# usb_relay_board.net
KiCad netlist of a schematic drawn in EAGLE
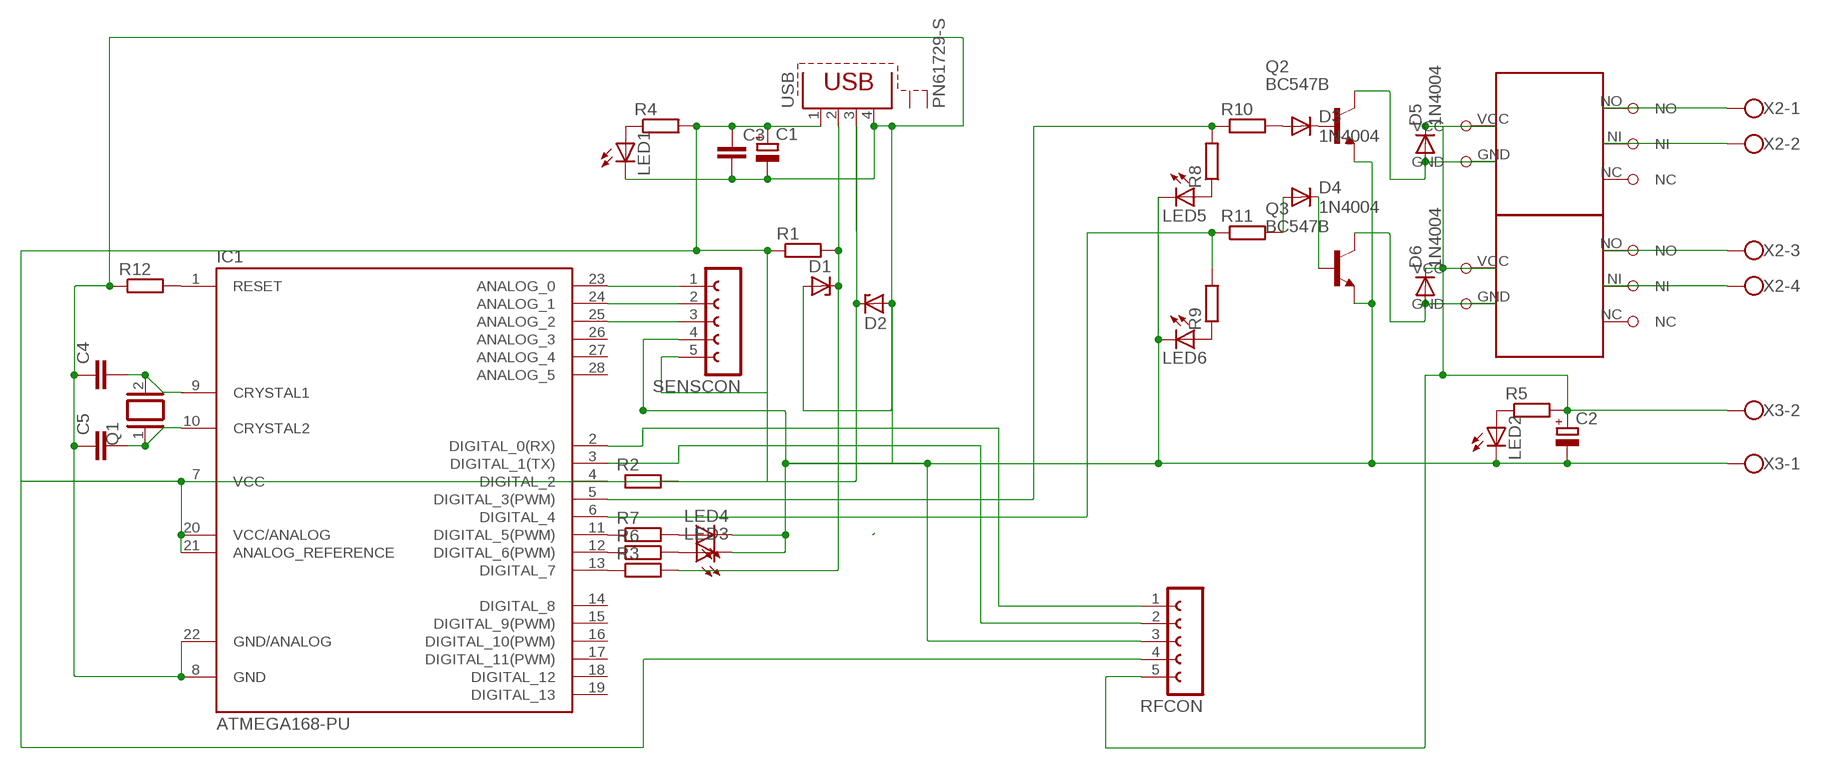
[diagram p0: schematic, sheet 1]

(export (version "E")
  (design (tool "Eeschema 10.0.6"))
  (components
    (comp (ref "C1")
      (value "CPOL-EUE2.5-7")
      (footprint "eagle-import:E2,5-7")
      (libsource (lib "eagle-import") (part "CPOL-EUE2.5-7"))
    )
    (comp (ref "C2")
      (value "CPOL-EUE5-10.5")
      (footprint "eagle-import:E5-10,5")
      (libsource (lib "eagle-import") (part "CPOL-EUE5-10.5"))
    )
    (comp (ref "C3")
      (value "C-EU075-032X103")
      (footprint "eagle-import:C075-032X103")
      (libsource (lib "eagle-import") (part "C-EU075-032X103"))
    )
    (comp (ref "C4")
      (value "C-EU075-032X103")
      (footprint "eagle-import:C075-032X103")
      (libsource (lib "eagle-import") (part "C-EU075-032X103"))
    )
    (comp (ref "C5")
      (value "C-EU075-032X103")
      (footprint "eagle-import:C075-032X103")
      (libsource (lib "eagle-import") (part "C-EU075-032X103"))
    )
    (comp (ref "D1")
      (value "ZENER-DIODEDO34-7")
      (footprint "eagle-import:DO34Z7")
      (libsource (lib "eagle-import") (part "ZENER-DIODEDO34-7"))
    )
    (comp (ref "D2")
      (value "ZENER-DIODEDO34-7")
      (footprint "eagle-import:DO34Z7")
      (libsource (lib "eagle-import") (part "ZENER-DIODEDO34-7"))
    )
    (comp (ref "D3")
      (value "1N4004")
      (footprint "eagle-import:DO41-10")
      (libsource (lib "eagle-import") (part "1N4004"))
    )
    (comp (ref "D4")
      (value "1N4004")
      (footprint "eagle-import:DO41-10")
      (libsource (lib "eagle-import") (part "1N4004"))
    )
    (comp (ref "D5")
      (value "1N4004")
      (footprint "eagle-import:DO41-10")
      (libsource (lib "eagle-import") (part "1N4004"))
    )
    (comp (ref "D6")
      (value "1N4004")
      (footprint "eagle-import:DO41-10")
      (libsource (lib "eagle-import") (part "1N4004"))
    )
    (comp (ref "IC1")
      (value "ATMEGA168-PU")
      (footprint "eagle-import:DIL28-3")
      (libsource (lib "eagle-import") (part "ATMEGA168-PU"))
    )
    (comp (ref "LED1")
      (value "LED3MM")
      (footprint "eagle-import:LED3MM")
      (libsource (lib "eagle-import") (part "LED3MM"))
    )
    (comp (ref "LED2")
      (value "LED3MM")
      (footprint "eagle-import:LED3MM")
      (libsource (lib "eagle-import") (part "LED3MM"))
    )
    (comp (ref "LED3")
      (value "LED3MM")
      (footprint "eagle-import:LED3MM")
      (libsource (lib "eagle-import") (part "LED3MM"))
    )
    (comp (ref "LED4")
      (value "LED3MM")
      (footprint "eagle-import:LED3MM")
      (libsource (lib "eagle-import") (part "LED3MM"))
    )
    (comp (ref "LED5")
      (value "LED3MM")
      (footprint "eagle-import:LED3MM")
      (libsource (lib "eagle-import") (part "LED3MM"))
    )
    (comp (ref "LED6")
      (value "LED3MM")
      (footprint "eagle-import:LED3MM")
      (libsource (lib "eagle-import") (part "LED3MM"))
    )
    (comp (ref "Q1")
      (value "XTAL/S")
      (footprint "eagle-import:QS")
      (libsource (lib "eagle-import") (part "XTAL/S"))
    )
    (comp (ref "Q2")
      (value "BC547B")
      (footprint "eagle-import:TO92")
      (libsource (lib "eagle-import") (part "BC547B"))
    )
    (comp (ref "Q3")
      (value "BC547B")
      (footprint "eagle-import:TO92")
      (libsource (lib "eagle-import") (part "BC547B"))
    )
    (comp (ref "R1")
      (value "R-EU_0204/7")
      (footprint "eagle-import:0204_7")
      (libsource (lib "eagle-import") (part "R-EU_0204/7"))
    )
    (comp (ref "R2")
      (value "R-EU_0204/7")
      (footprint "eagle-import:0204_7")
      (libsource (lib "eagle-import") (part "R-EU_0204/7"))
    )
    (comp (ref "R3")
      (value "R-EU_0204/7")
      (footprint "eagle-import:0204_7")
      (libsource (lib "eagle-import") (part "R-EU_0204/7"))
    )
    (comp (ref "R4")
      (value "R-EU_0204/7")
      (footprint "eagle-import:0204_7")
      (libsource (lib "eagle-import") (part "R-EU_0204/7"))
    )
    (comp (ref "R5")
      (value "R-EU_0204/7")
      (footprint "eagle-import:0204_7")
      (libsource (lib "eagle-import") (part "R-EU_0204/7"))
    )
    (comp (ref "R6")
      (value "R-EU_0204/7")
      (footprint "eagle-import:0204_7")
      (libsource (lib "eagle-import") (part "R-EU_0204/7"))
    )
    (comp (ref "R7")
      (value "R-EU_0204/7")
      (footprint "eagle-import:0204_7")
      (libsource (lib "eagle-import") (part "R-EU_0204/7"))
    )
    (comp (ref "R8")
      (value "R-EU_0204/7")
      (footprint "eagle-import:0204_7")
      (libsource (lib "eagle-import") (part "R-EU_0204/7"))
    )
    (comp (ref "R9")
      (value "R-EU_0204/7")
      (footprint "eagle-import:0204_7")
      (libsource (lib "eagle-import") (part "R-EU_0204/7"))
    )
    (comp (ref "R10")
      (value "R-EU_0204/7")
      (footprint "eagle-import:0204_7")
      (libsource (lib "eagle-import") (part "R-EU_0204/7"))
    )
    (comp (ref "R11")
      (value "R-EU_0204/7")
      (footprint "eagle-import:0204_7")
      (libsource (lib "eagle-import") (part "R-EU_0204/7"))
    )
    (comp (ref "R12")
      (value "R-EU_0204/7")
      (footprint "eagle-import:0204_7")
      (libsource (lib "eagle-import") (part "R-EU_0204/7"))
    )
    (comp (ref "RFCON")
      (value "FE05-1")
      (footprint "eagle-import:FE05-1")
      (libsource (lib "eagle-import") (part "FE05-1"))
    )
    (comp (ref "SENSCON")
      (value "FE05-1")
      (footprint "eagle-import:FE05-1")
      (libsource (lib "eagle-import") (part "FE05-1"))
    )
    (comp (ref "U$1")
      (value "RELAY")
      (footprint "eagle-import:RELAY")
      (libsource (lib "eagle-import") (part "RELAY"))
    )
    (comp (ref "U$2")
      (value "RELAY")
      (footprint "eagle-import:RELAY")
      (libsource (lib "eagle-import") (part "RELAY"))
    )
    (comp (ref "USB")
      (value "PN61729-S")
      (footprint "eagle-import:PN61729-S")
      (libsource (lib "eagle-import") (part "PN61729-S"))
    )
    (comp (ref "X2")
      (value "W237-4")
      (footprint "eagle-import:W237-4")
      (libsource (lib "eagle-import") (part "W237-4"))
    )
    (comp (ref "X3")
      (value "W237-102")
      (footprint "eagle-import:W237-102")
      (fields (field (name "MPN") "237-102"))
      (libsource (lib "eagle-import") (part "W237-102"))
    )
  )
  (nets
    (net (code "1") (name "Net-(D1-PadC)") (class "Default")
      (node (ref "D1") (pin "C") (pinfunction "C_C") (pintype "passive"))
      (node (ref "R1") (pin "2") (pinfunction "2_2") (pintype "passive"))
      (node (ref "R3") (pin "2") (pinfunction "2_2") (pintype "passive"))
      (node (ref "USB") (pin "2") (pinfunction "2_2") (pintype "passive"))
    )
    (net (code "2") (name "Net-(D2-PadC)") (class "Default")
      (node (ref "D2") (pin "C") (pinfunction "C_C") (pintype "passive"))
      (node (ref "R2") (pin "2") (pinfunction "2_2") (pintype "passive"))
      (node (ref "USB") (pin "3") (pinfunction "3_3") (pintype "passive"))
    )
    (net (code "3") (name "Net-(D3-PadA)") (class "Default")
      (node (ref "D3") (pin "A") (pinfunction "A_A") (pintype "passive"))
      (node (ref "R10") (pin "2") (pinfunction "2_2") (pintype "passive"))
    )
    (net (code "4") (name "Net-(D4-PadA)") (class "Default")
      (node (ref "D4") (pin "A") (pinfunction "A_A") (pintype "passive"))
      (node (ref "R11") (pin "2") (pinfunction "2_2") (pintype "passive"))
    )
    (net (code "5") (name "Net-(IC1-ANALOG_0)") (class "Default")
      (node (ref "IC1") (pin "23") (pinfunction "ANALOG_0_23") (pintype "bidirectional"))
      (node (ref "SENSCON") (pin "1") (pinfunction "1_1") (pintype "passive"))
    )
    (net (code "6") (name "Net-(IC1-ANALOG_1)") (class "Default")
      (node (ref "IC1") (pin "24") (pinfunction "ANALOG_1_24") (pintype "bidirectional"))
      (node (ref "SENSCON") (pin "2") (pinfunction "2_2") (pintype "passive"))
    )
    (net (code "7") (name "Net-(IC1-ANALOG_2)") (class "Default")
      (node (ref "IC1") (pin "25") (pinfunction "ANALOG_2_25") (pintype "bidirectional"))
      (node (ref "SENSCON") (pin "3") (pinfunction "3_3") (pintype "passive"))
    )
    (net (code "8") (name "Net-(IC1-ANALOG_REFERENCE)") (class "Default")
      (node (ref "C1") (pin "+") (pinfunction "+_+") (pintype "passive"))
      (node (ref "C3") (pin "1") (pinfunction "1_1") (pintype "passive"))
      (node (ref "IC1") (pin "20") (pinfunction "VCC/ANALOG_20") (pintype "passive"))
      (node (ref "IC1") (pin "21") (pinfunction "ANALOG_REFERENCE_21") (pintype "passive"))
      (node (ref "IC1") (pin "7") (pinfunction "VCC_7") (pintype "power_in"))
      (node (ref "R1") (pin "1") (pinfunction "1_1") (pintype "passive"))
      (node (ref "R4") (pin "2") (pinfunction "2_2") (pintype "passive"))
      (node (ref "SENSCON") (pin "5") (pinfunction "5_5") (pintype "passive"))
      (node (ref "USB") (pin "1") (pinfunction "1_1") (pintype "passive"))
    )
    (net (code "9") (name "Net-(IC1-CRYSTAL1)") (class "Default")
      (node (ref "C4") (pin "2") (pinfunction "2_2") (pintype "passive"))
      (node (ref "IC1") (pin "9") (pinfunction "CRYSTAL1_9") (pintype "bidirectional"))
      (node (ref "Q1") (pin "2") (pinfunction "2_2") (pintype "passive"))
    )
    (net (code "10") (name "Net-(IC1-CRYSTAL2)") (class "Default")
      (node (ref "C5") (pin "2") (pinfunction "2_2") (pintype "passive"))
      (node (ref "IC1") (pin "10") (pinfunction "CRYSTAL2_10") (pintype "bidirectional"))
      (node (ref "Q1") (pin "1") (pinfunction "1_1") (pintype "passive"))
    )
    (net (code "11") (name "Net-(IC1-DIGITAL_0(RX))") (class "Default")
      (node (ref "IC1") (pin "2") (pinfunction "DIGITAL_0(RX)_2") (pintype "bidirectional"))
      (node (ref "RFCON") (pin "1") (pinfunction "1_1") (pintype "passive"))
    )
    (net (code "12") (name "Net-(IC1-DIGITAL_1(TX))") (class "Default")
      (node (ref "IC1") (pin "3") (pinfunction "DIGITAL_1(TX)_3") (pintype "bidirectional"))
      (node (ref "RFCON") (pin "2") (pinfunction "2_2") (pintype "passive"))
    )
    (net (code "13") (name "Net-(IC1-DIGITAL_2)") (class "Default")
      (node (ref "IC1") (pin "4") (pinfunction "DIGITAL_2_4") (pintype "bidirectional"))
      (node (ref "R2") (pin "1") (pinfunction "1_1") (pintype "passive"))
    )
    (net (code "14") (name "Net-(IC1-DIGITAL_3(PWM))") (class "Default")
      (node (ref "IC1") (pin "5") (pinfunction "DIGITAL_3(PWM)_5") (pintype "bidirectional"))
      (node (ref "R10") (pin "1") (pinfunction "1_1") (pintype "passive"))
      (node (ref "R8") (pin "2") (pinfunction "2_2") (pintype "passive"))
    )
    (net (code "15") (name "Net-(IC1-DIGITAL_4)") (class "Default")
      (node (ref "IC1") (pin "6") (pinfunction "DIGITAL_4_6") (pintype "bidirectional"))
      (node (ref "R11") (pin "1") (pinfunction "1_1") (pintype "passive"))
      (node (ref "R9") (pin "2") (pinfunction "2_2") (pintype "passive"))
    )
    (net (code "16") (name "Net-(IC1-DIGITAL_5(PWM))") (class "Default")
      (node (ref "IC1") (pin "11") (pinfunction "DIGITAL_5(PWM)_11") (pintype "bidirectional"))
      (node (ref "R7") (pin "1") (pinfunction "1_1") (pintype "passive"))
    )
    (net (code "17") (name "Net-(IC1-DIGITAL_6(PWM))") (class "Default")
      (node (ref "IC1") (pin "12") (pinfunction "DIGITAL_6(PWM)_12") (pintype "bidirectional"))
      (node (ref "R6") (pin "1") (pinfunction "1_1") (pintype "passive"))
    )
    (net (code "18") (name "Net-(IC1-DIGITAL_7)") (class "Default")
      (node (ref "IC1") (pin "13") (pinfunction "DIGITAL_7_13") (pintype "bidirectional"))
      (node (ref "R3") (pin "1") (pinfunction "1_1") (pintype "passive"))
    )
    (net (code "19") (name "Net-(IC1-GND)") (class "Default")
      (node (ref "C1") (pin "-") (pinfunction "-_-") (pintype "passive"))
      (node (ref "C2") (pin "-") (pinfunction "-_-") (pintype "passive"))
      (node (ref "C3") (pin "2") (pinfunction "2_2") (pintype "passive"))
      (node (ref "C4") (pin "1") (pinfunction "1_1") (pintype "passive"))
      (node (ref "C5") (pin "1") (pinfunction "1_1") (pintype "passive"))
      (node (ref "D1") (pin "A") (pinfunction "A_A") (pintype "passive"))
      (node (ref "D2") (pin "A") (pinfunction "A_A") (pintype "passive"))
      (node (ref "IC1") (pin "22") (pinfunction "GND/ANALOG_22") (pintype "power_in"))
      (node (ref "IC1") (pin "8") (pinfunction "GND_8") (pintype "power_in"))
      (node (ref "LED1") (pin "K") (pinfunction "C_K") (pintype "passive"))
      (node (ref "LED2") (pin "K") (pinfunction "C_K") (pintype "passive"))
      (node (ref "LED3") (pin "K") (pinfunction "C_K") (pintype "passive"))
      (node (ref "LED4") (pin "K") (pinfunction "C_K") (pintype "passive"))
      (node (ref "LED5") (pin "K") (pinfunction "C_K") (pintype "passive"))
      (node (ref "LED6") (pin "K") (pinfunction "C_K") (pintype "passive"))
      (node (ref "Q2") (pin "1") (pinfunction "E_1") (pintype "passive"))
      (node (ref "Q3") (pin "1") (pinfunction "E_1") (pintype "passive"))
      (node (ref "R12") (pin "1") (pinfunction "1_1") (pintype "passive"))
      (node (ref "RFCON") (pin "3") (pinfunction "3_3") (pintype "passive"))
      (node (ref "SENSCON") (pin "4") (pinfunction "4_4") (pintype "passive"))
      (node (ref "USB") (pin "4") (pinfunction "4_4") (pintype "passive"))
      (node (ref "X3") (pin "1") (pinfunction "KL_1") (pintype "passive"))
    )
    (net (code "20") (name "Net-(IC1-RESET)") (class "Default")
      (node (ref "IC1") (pin "1") (pinfunction "RESET_1") (pintype "bidirectional"))
      (node (ref "R12") (pin "2") (pinfunction "2_2") (pintype "passive"))
    )
    (net (code "21") (name "Net-(LED1-PadA)") (class "Default")
      (node (ref "LED1") (pin "A") (pinfunction "A_A") (pintype "passive"))
      (node (ref "R4") (pin "1") (pinfunction "1_1") (pintype "passive"))
    )
    (net (code "22") (name "Net-(LED2-PadA)") (class "Default")
      (node (ref "LED2") (pin "A") (pinfunction "A_A") (pintype "passive"))
      (node (ref "R5") (pin "1") (pinfunction "1_1") (pintype "passive"))
    )
    (net (code "23") (name "Net-(LED3-PadA)") (class "Default")
      (node (ref "LED3") (pin "A") (pinfunction "A_A") (pintype "passive"))
      (node (ref "R6") (pin "2") (pinfunction "2_2") (pintype "passive"))
    )
    (net (code "24") (name "Net-(LED4-PadA)") (class "Default")
      (node (ref "LED4") (pin "A") (pinfunction "A_A") (pintype "passive"))
      (node (ref "R7") (pin "2") (pinfunction "2_2") (pintype "passive"))
    )
    (net (code "25") (name "Net-(LED5-PadA)") (class "Default")
      (node (ref "LED5") (pin "A") (pinfunction "A_A") (pintype "passive"))
      (node (ref "R8") (pin "1") (pinfunction "1_1") (pintype "passive"))
    )
    (net (code "26") (name "Net-(LED6-PadA)") (class "Default")
      (node (ref "LED6") (pin "A") (pinfunction "A_A") (pintype "passive"))
      (node (ref "R9") (pin "1") (pinfunction "1_1") (pintype "passive"))
    )
    (net (code "27") (name "Net-(Q2-B)") (class "Default")
      (node (ref "D3") (pin "C") (pinfunction "C_C") (pintype "passive"))
      (node (ref "Q2") (pin "2") (pinfunction "B_2") (pintype "passive"))
    )
    (net (code "28") (name "Net-(Q2-C)") (class "Default")
      (node (ref "D5") (pin "A") (pinfunction "A_A") (pintype "passive"))
      (node (ref "Q2") (pin "3") (pinfunction "C_3") (pintype "passive"))
      (node (ref "U$1") (pin "GND") (pinfunction "GND_GND") (pintype "bidirectional"))
    )
    (net (code "29") (name "Net-(Q3-B)") (class "Default")
      (node (ref "D4") (pin "C") (pinfunction "C_C") (pintype "passive"))
      (node (ref "Q3") (pin "2") (pinfunction "B_2") (pintype "passive"))
    )
    (net (code "30") (name "Net-(Q3-C)") (class "Default")
      (node (ref "D6") (pin "A") (pinfunction "A_A") (pintype "passive"))
      (node (ref "Q3") (pin "3") (pinfunction "C_3") (pintype "passive"))
      (node (ref "U$2") (pin "GND") (pinfunction "GND_GND") (pintype "bidirectional"))
    )
    (net (code "31") (name "Net-(X2A-KL)") (class "Default")
      (node (ref "U$1") (pin "NO") (pinfunction "NO_NO") (pintype "bidirectional"))
      (node (ref "X2") (pin "1") (pinfunction "KL_1") (pintype "passive"))
    )
    (net (code "32") (name "Net-(X2B-KL)") (class "Default")
      (node (ref "U$1") (pin "NI") (pinfunction "NI_NI") (pintype "bidirectional"))
      (node (ref "X2") (pin "2") (pinfunction "KL_2") (pintype "passive"))
    )
    (net (code "33") (name "Net-(X2C-KL)") (class "Default")
      (node (ref "U$2") (pin "NO") (pinfunction "NO_NO") (pintype "bidirectional"))
      (node (ref "X2") (pin "3") (pinfunction "KL_3") (pintype "passive"))
    )
    (net (code "34") (name "Net-(X2D-KL)") (class "Default")
      (node (ref "U$2") (pin "NI") (pinfunction "NI_NI") (pintype "bidirectional"))
      (node (ref "X2") (pin "4") (pinfunction "KL_4") (pintype "passive"))
    )
    (net (code "35") (name "Net-(X3B-KL)") (class "Default")
      (node (ref "C2") (pin "+") (pinfunction "+_+") (pintype "passive"))
      (node (ref "D5") (pin "C") (pinfunction "C_C") (pintype "passive"))
      (node (ref "D6") (pin "C") (pinfunction "C_C") (pintype "passive"))
      (node (ref "R5") (pin "2") (pinfunction "2_2") (pintype "passive"))
      (node (ref "RFCON") (pin "5") (pinfunction "5_5") (pintype "passive"))
      (node (ref "U$1") (pin "VCC") (pinfunction "VCC_VCC") (pintype "bidirectional"))
      (node (ref "U$2") (pin "VCC") (pinfunction "VCC_VCC") (pintype "bidirectional"))
      (node (ref "X3") (pin "2") (pinfunction "KL_2") (pintype "passive"))
    )
    (net (code "36") (name "unconnected-(IC1-ANALOG_3-Pad26)") (class "Default")
      (node (ref "IC1") (pin "26") (pinfunction "ANALOG_3_26") (pintype "bidirectional"))
    )
    (net (code "37") (name "unconnected-(IC1-ANALOG_4-Pad27)") (class "Default")
      (node (ref "IC1") (pin "27") (pinfunction "ANALOG_4_27") (pintype "bidirectional"))
    )
    (net (code "38") (name "unconnected-(IC1-ANALOG_5-Pad28)") (class "Default")
      (node (ref "IC1") (pin "28") (pinfunction "ANALOG_5_28") (pintype "bidirectional"))
    )
    (net (code "39") (name "unconnected-(IC1-DIGITAL_8-Pad14)") (class "Default")
      (node (ref "IC1") (pin "14") (pinfunction "DIGITAL_8_14") (pintype "bidirectional"))
    )
    (net (code "40") (name "unconnected-(IC1-DIGITAL_9(PWM)-Pad15)") (class "Default")
      (node (ref "IC1") (pin "15") (pinfunction "DIGITAL_9(PWM)_15") (pintype "bidirectional"))
    )
    (net (code "41") (name "unconnected-(IC1-DIGITAL_10(PWM)-Pad16)") (class "Default")
      (node (ref "IC1") (pin "16") (pinfunction "DIGITAL_10(PWM)_16") (pintype "bidirectional"))
    )
    (net (code "42") (name "unconnected-(IC1-DIGITAL_11(PWM)-Pad17)") (class "Default")
      (node (ref "IC1") (pin "17") (pinfunction "DIGITAL_11(PWM)_17") (pintype "bidirectional"))
    )
    (net (code "43") (name "unconnected-(IC1-DIGITAL_12-Pad18)") (class "Default")
      (node (ref "IC1") (pin "18") (pinfunction "DIGITAL_12_18") (pintype "bidirectional"))
    )
    (net (code "44") (name "unconnected-(IC1-DIGITAL_13-Pad19)") (class "Default")
      (node (ref "IC1") (pin "19") (pinfunction "DIGITAL_13_19") (pintype "bidirectional"))
    )
    (net (code "45") (name "unconnected-(RFCON-Pad4)") (class "Default")
      (node (ref "RFCON") (pin "4") (pinfunction "4_4") (pintype "passive"))
    )
    (net (code "46") (name "unconnected-(U$1-PadNC)") (class "Default")
      (node (ref "U$1") (pin "NC") (pinfunction "NC_NC") (pintype "bidirectional"))
    )
    (net (code "47") (name "unconnected-(U$2-PadNC)") (class "Default")
      (node (ref "U$2") (pin "NC") (pinfunction "NC_NC") (pintype "bidirectional"))
    )
    (net (code "48") (name "unconnected-(USB-PadS1)") (class "Default")
      (node (ref "USB") (pin "S1") (pinfunction "S1_S1") (pintype "passive"))
    )
    (net (code "49") (name "unconnected-(USB-PadS2)") (class "Default")
      (node (ref "USB") (pin "S2") (pinfunction "S2_S2") (pintype "passive"))
    )
  )
)
